# pcb.net
KiCad netlist of a schematic drawn in EasyEDA Pro
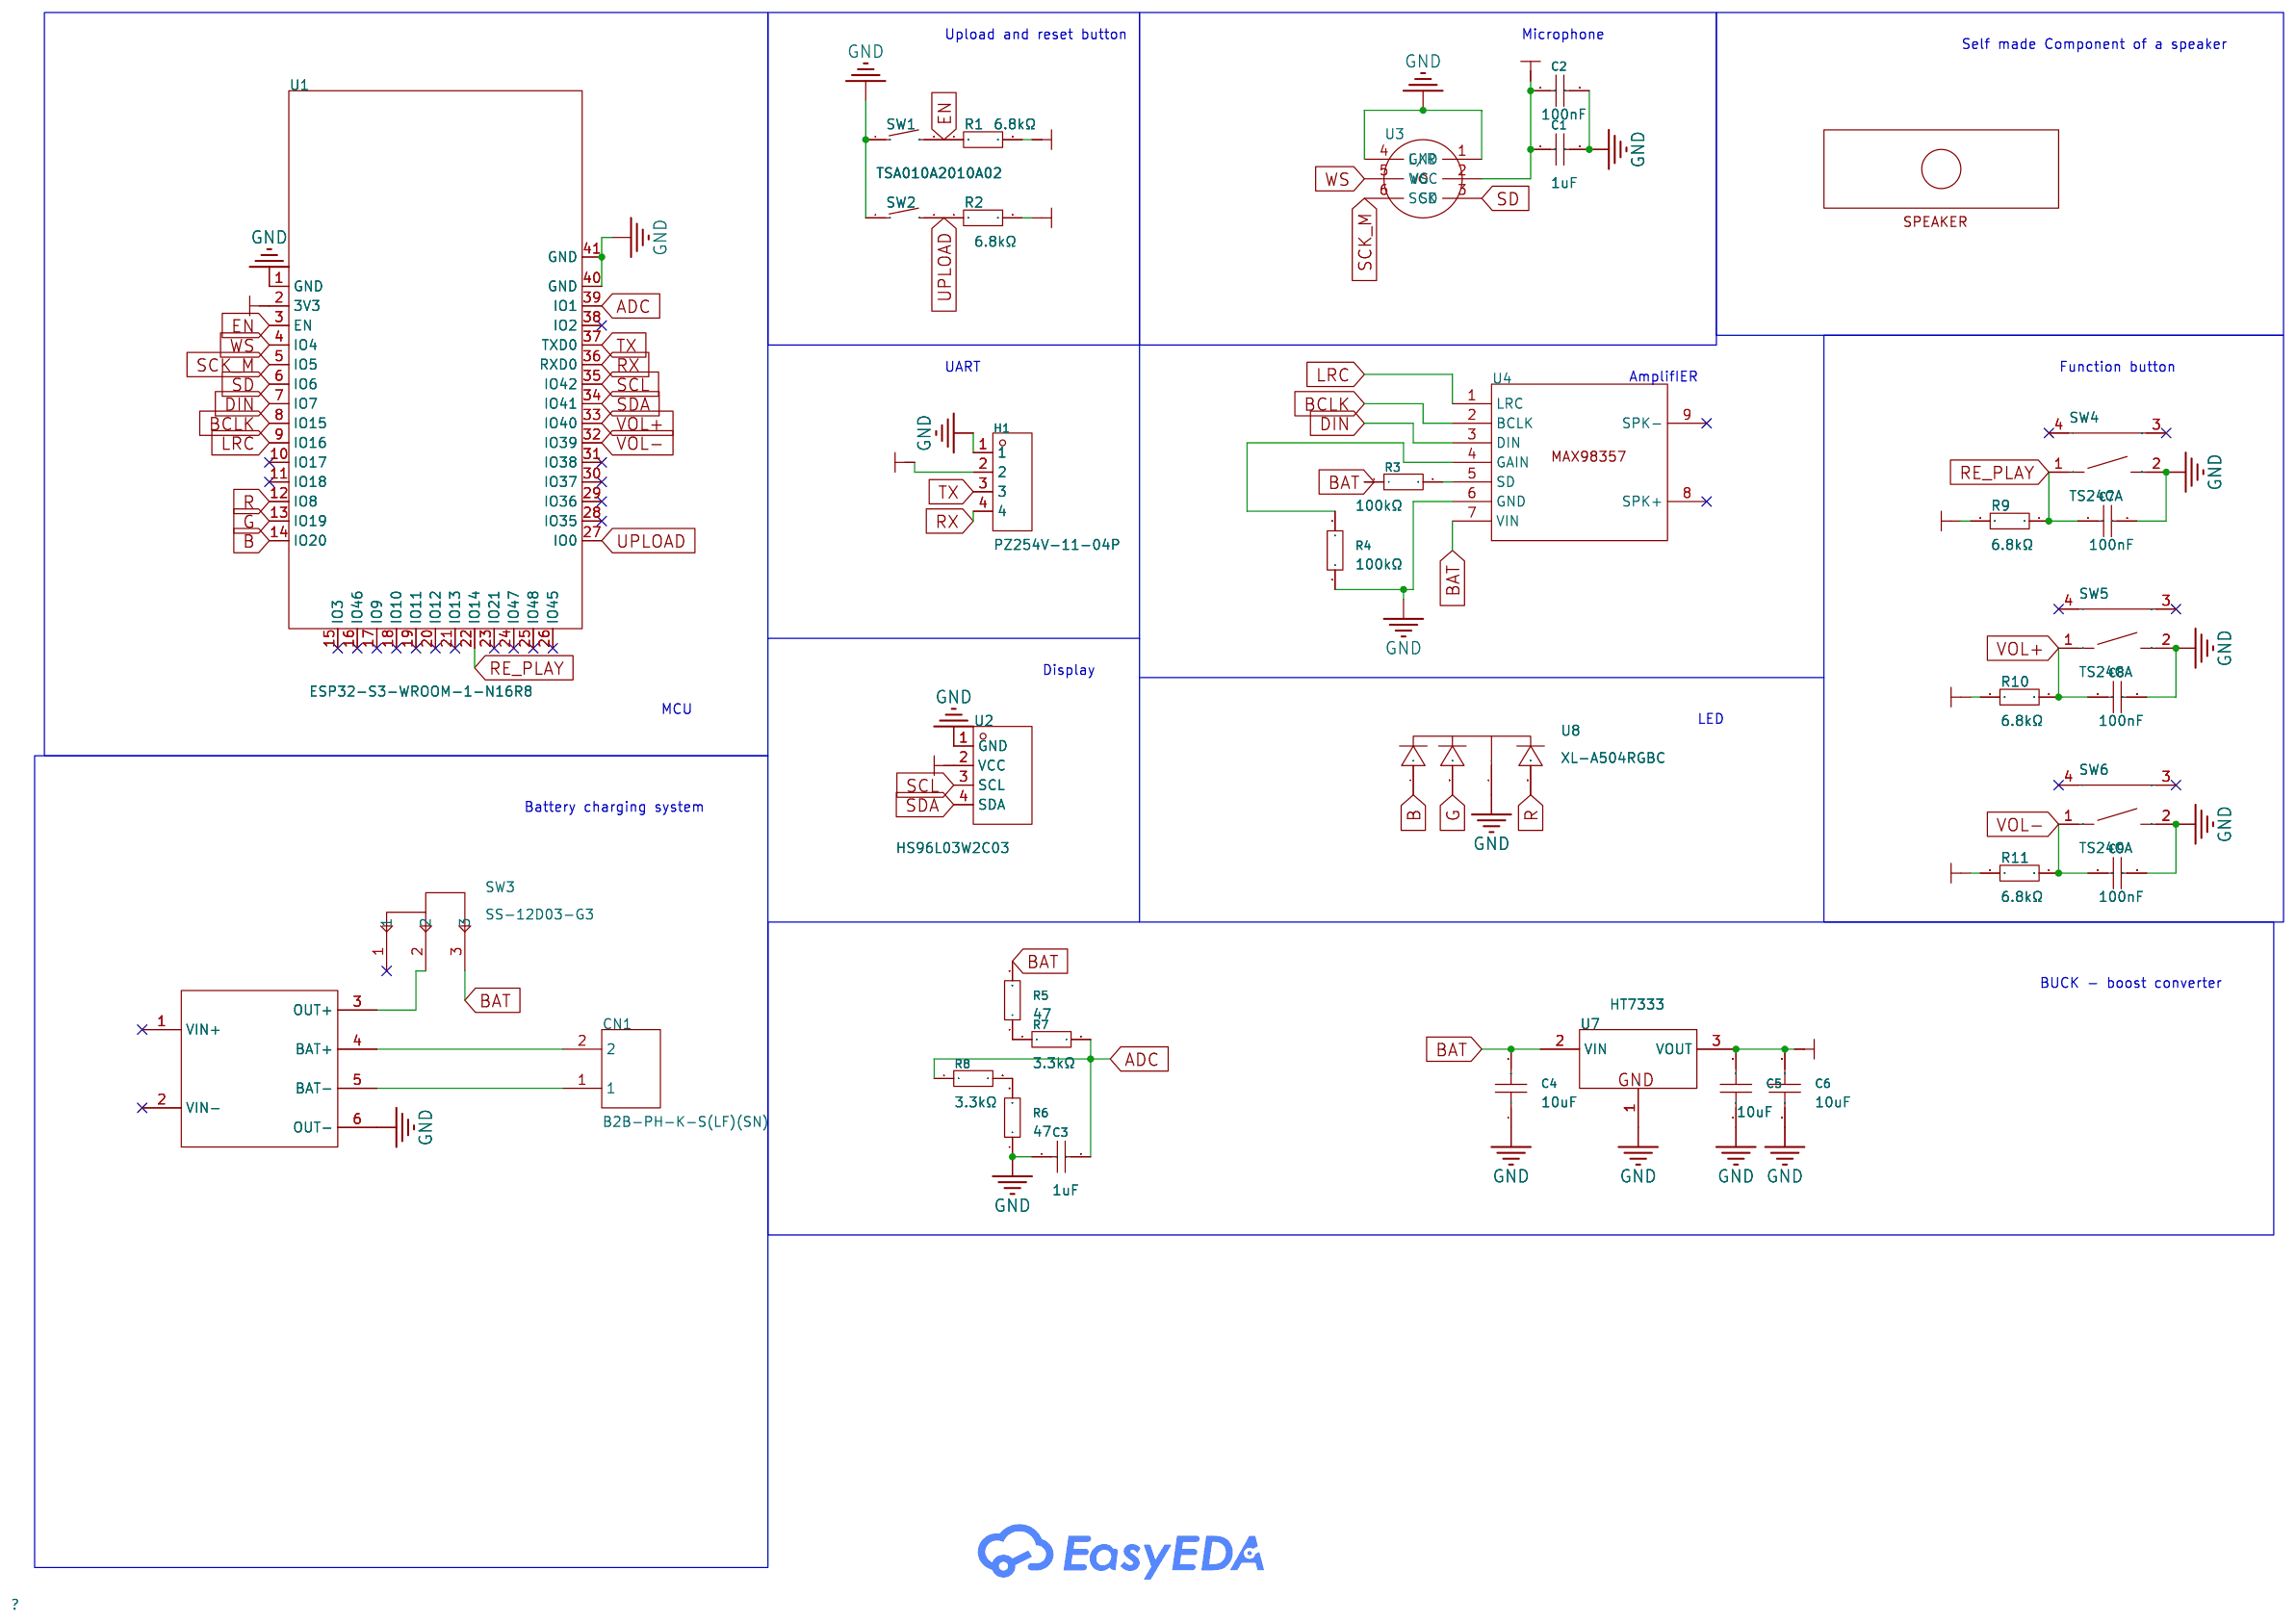
[diagram p0: schematic sheet]

(export (version "E")
  (design (tool "Eeschema 10.0.6"))
  (components
    (comp (ref "C1")
      (value "1uF")
      (footprint "easyedapro:C0805")
      (description "Capacitance:1uF Tolerance:±10% Tolerance:±10% Voltage Rating:50V Temperature Coefficient:X7R")
      (fields
        (field (name "Manufacturer Part") "CL21B105KBFNNNE")
        (field (name "Manufacturer") "SAMSUNG(三星)")
      )
      (libsource (lib "easyedapro") (part "CL21B105KBFNNNE"))
    )
    (comp (ref "C2")
      (value "100nF")
      (footprint "easyedapro:C1206")
      (description "Capacitance:100nF Tolerance:±10% Tolerance:±10% Voltage Rating:50V Temperature Coefficient:X7R")
      (fields
        (field (name "Manufacturer Part") "CL31B104KBCNNNC")
        (field (name "Manufacturer") "SAMSUNG(三星)")
      )
      (libsource (lib "easyedapro") (part "CL31B104KBCNNNC"))
    )
    (comp (ref "C3")
      (value "1uF")
      (footprint "easyedapro:C0805")
      (description "Capacitance:1uF Tolerance:±10% Tolerance:±10% Voltage Rating:50V Temperature Coefficient:X7R")
      (fields
        (field (name "Manufacturer Part") "CL21B105KBFNNNE")
        (field (name "Manufacturer") "SAMSUNG(三星)")
      )
      (libsource (lib "easyedapro") (part "CL21B105KBFNNNE"))
    )
    (comp (ref "C4")
      (value "10uF")
      (footprint "easyedapro:C0603")
      (description "Capacitance:10uF Tolerance:±20% Tolerance:±20% Voltage Rating:25V Temperature Coefficient:X5R")
      (fields
        (field (name "Manufacturer Part") "CL10A106MA8NRNC")
        (field (name "Manufacturer") "SAMSUNG(三星)")
      )
      (libsource (lib "easyedapro") (part "CL10A106MA8NRNC"))
    )
    (comp (ref "C5")
      (value "10uF")
      (footprint "easyedapro:C0603")
      (description "Capacitance:10uF Tolerance:±20% Tolerance:±20% Voltage Rating:25V Temperature Coefficient:X5R")
      (fields
        (field (name "Manufacturer Part") "CL10A106MA8NRNC")
        (field (name "Manufacturer") "SAMSUNG(三星)")
      )
      (libsource (lib "easyedapro") (part "CL10A106MA8NRNC"))
    )
    (comp (ref "C6")
      (value "10uF")
      (footprint "easyedapro:C0603")
      (description "Capacitance:10uF Tolerance:±20% Tolerance:±20% Voltage Rating:25V Temperature Coefficient:X5R")
      (fields
        (field (name "Manufacturer Part") "CL10A106MA8NRNC")
        (field (name "Manufacturer") "SAMSUNG(三星)")
      )
      (libsource (lib "easyedapro") (part "CL10A106MA8NRNC"))
    )
    (comp (ref "C7")
      (value "100nF")
      (footprint "easyedapro:C1206")
      (description "Capacitance:100nF Tolerance:±10% Tolerance:±10% Voltage Rating:50V Temperature Coefficient:X7R")
      (fields
        (field (name "Manufacturer Part") "CL31B104KBCNNNC")
        (field (name "Manufacturer") "SAMSUNG(三星)")
      )
      (libsource (lib "easyedapro") (part "CL31B104KBCNNNC"))
    )
    (comp (ref "C8")
      (value "100nF")
      (footprint "easyedapro:C1206")
      (description "Capacitance:100nF Tolerance:±10% Tolerance:±10% Voltage Rating:50V Temperature Coefficient:X7R")
      (fields
        (field (name "Manufacturer Part") "CL31B104KBCNNNC")
        (field (name "Manufacturer") "SAMSUNG(三星)")
      )
      (libsource (lib "easyedapro") (part "CL31B104KBCNNNC"))
    )
    (comp (ref "C9")
      (value "100nF")
      (footprint "easyedapro:C1206")
      (description "Capacitance:100nF Tolerance:±10% Tolerance:±10% Voltage Rating:50V Temperature Coefficient:X7R")
      (fields
        (field (name "Manufacturer Part") "CL31B104KBCNNNC")
        (field (name "Manufacturer") "SAMSUNG(三星)")
      )
      (libsource (lib "easyedapro") (part "CL31B104KBCNNNC"))
    )
    (comp (ref "CN1")
      (value "B2B-PH-K-S(LF)(SN)")
      (footprint "easyedapro:CONN-TH_B2B-PH-K-S")
      (fields (field (name "Manufacturer") "JST"))
      (libsource (lib "easyedapro") (part "B2B-PH-K-S(LF)(SN)"))
    )
    (comp (ref "H1")
      (value "PZ254V-11-04P")
      (footprint "easyedapro:HDR-TH_4P-P2.54-V-M")
      (fields (field (name "Manufacturer") "XFCN(兴飞)"))
      (libsource (lib "easyedapro") (part "PZ254V-11-04P_C2691448"))
    )
    (comp (ref "R1")
      (value "6.8kΩ")
      (footprint "easyedapro:R0603")
      (fields (field (name "Manufacturer Part") "RC0603FR-071KL") (field (name "Manufacturer") "YAGEO(国巨)"))
      (libsource (lib "easyedapro") (part "RC0603FR-071KL"))
    )
    (comp (ref "R2")
      (value "6.8kΩ")
      (footprint "easyedapro:R0603")
      (fields (field (name "Manufacturer Part") "RC0603FR-071KL") (field (name "Manufacturer") "YAGEO(国巨)"))
      (libsource (lib "easyedapro") (part "RC0603FR-071KL"))
    )
    (comp (ref "R3")
      (value "100kΩ")
      (footprint "easyedapro:R0603")
      (fields (field (name "Manufacturer Part") "RC0603FR-07100KL") (field (name "Manufacturer") "YAGEO(国巨)"))
      (libsource (lib "easyedapro") (part "RC0603FR-07100KL"))
    )
    (comp (ref "R4")
      (value "100kΩ")
      (footprint "easyedapro:R0603")
      (fields (field (name "Manufacturer Part") "RC0603FR-07100KL") (field (name "Manufacturer") "YAGEO(国巨)"))
      (libsource (lib "easyedapro") (part "RC0603FR-07100KL"))
    )
    (comp (ref "R5")
      (value "47")
      (footprint "easyedapro:R1206")
      (fields
        (field (name "Manufacturer Part") "1206W4F100KT5E")
        (field (name "Manufacturer") "UNI-ROYAL(厚声)")
      )
      (libsource (lib "easyedapro") (part "1206W4F100KT5E"))
    )
    (comp (ref "R6")
      (value "47")
      (footprint "easyedapro:R1206")
      (fields
        (field (name "Manufacturer Part") "1206W4F100KT5E")
        (field (name "Manufacturer") "UNI-ROYAL(厚声)")
      )
      (libsource (lib "easyedapro") (part "1206W4F100KT5E"))
    )
    (comp (ref "R7")
      (value "3.3kΩ")
      (footprint "easyedapro:R0603")
      (fields
        (field (name "Manufacturer Part") "0603WAF3301T5E")
        (field (name "Manufacturer") "UNI-ROYAL(厚声)")
      )
      (libsource (lib "easyedapro") (part "0603WAF3301T5E"))
    )
    (comp (ref "R8")
      (value "3.3kΩ")
      (footprint "easyedapro:R0603")
      (fields
        (field (name "Manufacturer Part") "0603WAF3301T5E")
        (field (name "Manufacturer") "UNI-ROYAL(厚声)")
      )
      (libsource (lib "easyedapro") (part "0603WAF3301T5E"))
    )
    (comp (ref "R9")
      (value "6.8kΩ")
      (footprint "easyedapro:R0603")
      (fields (field (name "Manufacturer Part") "RC0603FR-071KL") (field (name "Manufacturer") "YAGEO(国巨)"))
      (libsource (lib "easyedapro") (part "RC0603FR-071KL"))
    )
    (comp (ref "R10")
      (value "6.8kΩ")
      (footprint "easyedapro:R0603")
      (fields (field (name "Manufacturer Part") "RC0603FR-071KL") (field (name "Manufacturer") "YAGEO(国巨)"))
      (libsource (lib "easyedapro") (part "RC0603FR-071KL"))
    )
    (comp (ref "R11")
      (value "6.8kΩ")
      (footprint "easyedapro:R0603")
      (fields (field (name "Manufacturer Part") "RC0603FR-071KL") (field (name "Manufacturer") "YAGEO(国巨)"))
      (libsource (lib "easyedapro") (part "RC0603FR-071KL"))
    )
    (comp (ref "SW1")
      (value "TSA010A2010A02")
      (footprint "easyedapro:KEY-SMD_L3.9-W3.0-LS5.0")
      (fields (field (name "Manufacturer") "BZCN(博众电气)"))
      (libsource (lib "easyedapro") (part "TSA010A2010A02"))
    )
    (comp (ref "SW2")
      (value "TSA010A2010A02")
      (footprint "easyedapro:KEY-SMD_L3.9-W3.0-LS5.0")
      (fields (field (name "Manufacturer") "BZCN(博众电气)"))
      (libsource (lib "easyedapro") (part "TSA010A2010A02"))
    )
    (comp (ref "SW3")
      (value "SS-12D03-G3")
      (footprint "easyedapro:SW-TH_3P-L8.5-W3.5-P2.50_SS-12D03-G3_C5160828")
      (fields (field (name "Manufacturer") "DEALON(德艺隆)"))
      (libsource (lib "easyedapro") (part "SS-12D03-G3_C5160828"))
    )
    (comp (ref "SW4")
      (value "TS24CA")
      (footprint "easyedapro:SW-SMD_2P-TS24CA")
      (fields (field (name "Manufacturer") "SHOU HAN(首韩)"))
      (libsource (lib "easyedapro") (part "TS24CA"))
    )
    (comp (ref "SW5")
      (value "TS24CA")
      (footprint "easyedapro:SW-SMD_2P-TS24CA")
      (fields (field (name "Manufacturer") "SHOU HAN(首韩)"))
      (libsource (lib "easyedapro") (part "TS24CA"))
    )
    (comp (ref "SW6")
      (value "TS24CA")
      (footprint "easyedapro:SW-SMD_2P-TS24CA")
      (fields (field (name "Manufacturer") "SHOU HAN(首韩)"))
      (libsource (lib "easyedapro") (part "TS24CA"))
    )
    (comp (ref "U1")
      (value "ESP32-S3-WROOM-1-N16R8")
      (footprint "easyedapro:WIRELM-SMD_ESP32-S3-WROOM-1")
      (fields (field (name "Manufacturer") "ESPRESSIF(乐鑫)"))
      (libsource (lib "easyedapro") (part "ESP32-S3-WROOM-1(N16R8)"))
    )
    (comp (ref "U2")
      (value "HS96L03W2C03")
      (footprint "easyedapro:OLED-TH_L27.8-W27.2-P2.54_C9900033791")
      (fields (field (name "Manufacturer") "HS(汉昇)"))
      (libsource (lib "easyedapro") (part "HS96L03W2C03"))
    )
    (comp (ref "U3")
      (value "~")
      (footprint "easyedapro:INMP441")
      (libsource (lib "easyedapro") (part "INMP441"))
    )
    (comp (ref "U4")
      (value "~")
      (footprint "easyedapro:MAX98357")
      (libsource (lib "easyedapro") (part "MAX98357"))
    )
    (comp (ref "U5")
      (value "~")
      (footprint "easyedapro:SPEAKER")
      (libsource (lib "easyedapro") (part "SPEAKER"))
    )
    (comp (ref "U6")
      (value "~")
      (footprint "easyedapro:TP4056 Carging Module")
      (libsource (lib "easyedapro") (part "TP4056 Charging Module"))
    )
    (comp (ref "U7")
      (value "HT7333")
      (footprint "easyedapro:SOT-89-3_L4.5-W2.5-P1.50-LS4.1-BR")
      (description "Output Type:-")
      (libsource (lib "easyedapro") (part "HT7333"))
    )
    (comp (ref "U8")
      (value "XL-A504RGBC")
      (footprint "easyedapro:LED-TH_4P-BD5.8-P1.25_DM-50346EH-73826CC-05RGB-BML60-D")
      (fields (field (name "Manufacturer") "XINGLIGHT(成兴光)"))
      (libsource (lib "easyedapro") (part "XL-A504RGBC"))
    )
  )
  (nets
    (net (code "1") (name "+3V3") (class "Default")
      (node (ref "C1") (pin "1") (pinfunction "1_1") (pintype "input"))
      (node (ref "C2") (pin "1") (pinfunction "1_1") (pintype "input"))
      (node (ref "C5") (pin "2") (pinfunction "2_2") (pintype "input"))
      (node (ref "C6") (pin "2") (pinfunction "2_2") (pintype "input"))
      (node (ref "H1") (pin "2") (pinfunction "2_2") (pintype "input"))
      (node (ref "R1") (pin "2") (pinfunction "2_2") (pintype "input"))
      (node (ref "R10") (pin "2") (pinfunction "2_2") (pintype "input"))
      (node (ref "R11") (pin "2") (pinfunction "2_2") (pintype "input"))
      (node (ref "R2") (pin "2") (pinfunction "2_2") (pintype "input"))
      (node (ref "R9") (pin "2") (pinfunction "2_2") (pintype "input"))
      (node (ref "U1") (pin "2") (pinfunction "3V3_2") (pintype "unspecified"))
      (node (ref "U2") (pin "2") (pinfunction "VCC_2") (pintype "unspecified"))
      (node (ref "U3") (pin "2") (pinfunction "VCC_2") (pintype "input"))
      (node (ref "U7") (pin "3") (pinfunction "VOUT_3") (pintype "unspecified"))
    )
    (net (code "2") (name "ADC") (class "Default")
      (node (ref "C3") (pin "2") (pinfunction "2_2") (pintype "input"))
      (node (ref "R7") (pin "2") (pinfunction "2_2") (pintype "input"))
      (node (ref "R8") (pin "1") (pinfunction "1_1") (pintype "input"))
      (node (ref "U1") (pin "39") (pinfunction "IO1_39") (pintype "unspecified"))
    )
    (net (code "3") (name "B") (class "Default")
      (node (ref "U1") (pin "14") (pinfunction "IO20_14") (pintype "unspecified"))
      (node (ref "U8") (pin "4") (pinfunction "4_4") (pintype "unspecified"))
    )
    (net (code "4") (name "BAT") (class "Default")
      (node (ref "C4") (pin "2") (pinfunction "2_2") (pintype "input"))
      (node (ref "R3") (pin "1") (pinfunction "1_1") (pintype "input"))
      (node (ref "R5") (pin "2") (pinfunction "2_2") (pintype "input"))
      (node (ref "SW3") (pin "3") (pinfunction "3_3") (pintype "unspecified"))
      (node (ref "U4") (pin "7") (pinfunction "VIN_7") (pintype "input"))
      (node (ref "U7") (pin "2") (pinfunction "VIN_2") (pintype "unspecified"))
    )
    (net (code "5") (name "BCLK") (class "Default")
      (node (ref "U1") (pin "8") (pinfunction "IO15_8") (pintype "unspecified"))
      (node (ref "U4") (pin "2") (pinfunction "BCLK_2") (pintype "input"))
    )
    (net (code "6") (name "DIN") (class "Default")
      (node (ref "U1") (pin "7") (pinfunction "IO7_7") (pintype "unspecified"))
      (node (ref "U4") (pin "3") (pinfunction "DIN_3") (pintype "input"))
    )
    (net (code "7") (name "EN") (class "Default")
      (node (ref "R1") (pin "1") (pinfunction "1_1") (pintype "input"))
      (node (ref "SW1") (pin "2") (pinfunction "2_2") (pintype "unspecified"))
      (node (ref "U1") (pin "3") (pinfunction "EN_3") (pintype "unspecified"))
    )
    (net (code "8") (name "G") (class "Default")
      (node (ref "U1") (pin "13") (pinfunction "IO19_13") (pintype "unspecified"))
      (node (ref "U8") (pin "3") (pinfunction "3_3") (pintype "unspecified"))
    )
    (net (code "9") (name "GND") (class "Default")
      (node (ref "C1") (pin "2") (pinfunction "2_2") (pintype "input"))
      (node (ref "C2") (pin "2") (pinfunction "2_2") (pintype "input"))
      (node (ref "C3") (pin "1") (pinfunction "1_1") (pintype "input"))
      (node (ref "C4") (pin "1") (pinfunction "1_1") (pintype "input"))
      (node (ref "C5") (pin "1") (pinfunction "1_1") (pintype "input"))
      (node (ref "C6") (pin "1") (pinfunction "1_1") (pintype "input"))
      (node (ref "C7") (pin "2") (pinfunction "2_2") (pintype "input"))
      (node (ref "C8") (pin "2") (pinfunction "2_2") (pintype "input"))
      (node (ref "C9") (pin "2") (pinfunction "2_2") (pintype "input"))
      (node (ref "H1") (pin "1") (pinfunction "1_1") (pintype "input"))
      (node (ref "R4") (pin "1") (pinfunction "1_1") (pintype "input"))
      (node (ref "R6") (pin "1") (pinfunction "1_1") (pintype "input"))
      (node (ref "SW1") (pin "1") (pinfunction "1_1") (pintype "unspecified"))
      (node (ref "SW2") (pin "1") (pinfunction "1_1") (pintype "unspecified"))
      (node (ref "SW4") (pin "2") (pinfunction "2_2") (pintype "unspecified"))
      (node (ref "SW5") (pin "2") (pinfunction "2_2") (pintype "unspecified"))
      (node (ref "SW6") (pin "2") (pinfunction "2_2") (pintype "unspecified"))
      (node (ref "U1") (pin "1") (pinfunction "GND_1") (pintype "unspecified"))
      (node (ref "U1") (pin "40") (pinfunction "GND_40") (pintype "unspecified"))
      (node (ref "U1") (pin "41") (pinfunction "GND_41") (pintype "unspecified"))
      (node (ref "U2") (pin "1") (pinfunction "GND_1") (pintype "unspecified"))
      (node (ref "U3") (pin "1") (pinfunction "GND_1") (pintype "input"))
      (node (ref "U3") (pin "4") (pinfunction "L/R_4") (pintype "input"))
      (node (ref "U4") (pin "6") (pinfunction "GND_6") (pintype "input"))
      (node (ref "U6") (pin "6") (pinfunction "OUT-_6") (pintype "input"))
      (node (ref "U7") (pin "1") (pinfunction "GND_1") (pintype "unspecified"))
      (node (ref "U8") (pin "1") (pinfunction "-_1") (pintype "unspecified"))
    )
    (net (code "10") (name "LRC") (class "Default")
      (node (ref "U1") (pin "9") (pinfunction "IO16_9") (pintype "unspecified"))
      (node (ref "U4") (pin "1") (pinfunction "LRC_1") (pintype "input"))
    )
    (net (code "11") (name "Net-(R5-Pad1)") (class "Default")
      (node (ref "R5") (pin "1") (pinfunction "1_1") (pintype "input"))
      (node (ref "R7") (pin "1") (pinfunction "1_1") (pintype "input"))
    )
    (net (code "12") (name "Net-(R6-Pad2)") (class "Default")
      (node (ref "R6") (pin "2") (pinfunction "2_2") (pintype "input"))
      (node (ref "R8") (pin "2") (pinfunction "2_2") (pintype "input"))
    )
    (net (code "13") (name "Net-(U4-GAIN)") (class "Default")
      (node (ref "R4") (pin "2") (pinfunction "2_2") (pintype "input"))
      (node (ref "U4") (pin "4") (pinfunction "GAIN_4") (pintype "input"))
    )
    (net (code "14") (name "Net-(U4-SD)") (class "Default")
      (node (ref "R3") (pin "2") (pinfunction "2_2") (pintype "input"))
      (node (ref "U4") (pin "5") (pinfunction "SD_5") (pintype "input"))
    )
    (net (code "15") (name "Net-(U6-BAT+)") (class "Default")
      (node (ref "CN1") (pin "2") (pinfunction "2_2") (pintype "input"))
      (node (ref "U6") (pin "4") (pinfunction "BAT+_4") (pintype "input"))
    )
    (net (code "16") (name "Net-(U6-BAT-)") (class "Default")
      (node (ref "CN1") (pin "1") (pinfunction "1_1") (pintype "input"))
      (node (ref "U6") (pin "5") (pinfunction "BAT-_5") (pintype "input"))
    )
    (net (code "17") (name "Net-(U6-OUT+)") (class "Default")
      (node (ref "SW3") (pin "2") (pinfunction "2_2") (pintype "unspecified"))
      (node (ref "U6") (pin "3") (pinfunction "OUT+_3") (pintype "input"))
    )
    (net (code "18") (name "R") (class "Default")
      (node (ref "U1") (pin "12") (pinfunction "IO8_12") (pintype "unspecified"))
      (node (ref "U8") (pin "2") (pinfunction "2_2") (pintype "unspecified"))
    )
    (net (code "19") (name "RE_PLAY") (class "Default")
      (node (ref "C7") (pin "1") (pinfunction "1_1") (pintype "input"))
      (node (ref "R9") (pin "1") (pinfunction "1_1") (pintype "input"))
      (node (ref "SW4") (pin "1") (pinfunction "1_1") (pintype "unspecified"))
      (node (ref "U1") (pin "22") (pinfunction "IO14_22") (pintype "unspecified"))
    )
    (net (code "20") (name "RX") (class "Default")
      (node (ref "H1") (pin "4") (pinfunction "4_4") (pintype "input"))
      (node (ref "U1") (pin "36") (pinfunction "RXD0_36") (pintype "unspecified"))
    )
    (net (code "21") (name "SCK_M") (class "Default")
      (node (ref "U1") (pin "5") (pinfunction "IO5_5") (pintype "unspecified"))
      (node (ref "U3") (pin "6") (pinfunction "SCK_6") (pintype "input"))
    )
    (net (code "22") (name "SCL") (class "Default")
      (node (ref "U1") (pin "35") (pinfunction "IO42_35") (pintype "unspecified"))
      (node (ref "U2") (pin "3") (pinfunction "SCL_3") (pintype "unspecified"))
    )
    (net (code "23") (name "SD") (class "Default")
      (node (ref "U1") (pin "6") (pinfunction "IO6_6") (pintype "unspecified"))
      (node (ref "U3") (pin "3") (pinfunction "SD_3") (pintype "input"))
    )
    (net (code "24") (name "SDA") (class "Default")
      (node (ref "U1") (pin "34") (pinfunction "IO41_34") (pintype "unspecified"))
      (node (ref "U2") (pin "4") (pinfunction "SDA_4") (pintype "unspecified"))
    )
    (net (code "25") (name "TX") (class "Default")
      (node (ref "H1") (pin "3") (pinfunction "3_3") (pintype "input"))
      (node (ref "U1") (pin "37") (pinfunction "TXD0_37") (pintype "unspecified"))
    )
    (net (code "26") (name "UPLOAD") (class "Default")
      (node (ref "R2") (pin "1") (pinfunction "1_1") (pintype "input"))
      (node (ref "SW2") (pin "2") (pinfunction "2_2") (pintype "unspecified"))
      (node (ref "U1") (pin "27") (pinfunction "IO0_27") (pintype "unspecified"))
    )
    (net (code "27") (name "VOL+") (class "Default")
      (node (ref "C8") (pin "1") (pinfunction "1_1") (pintype "input"))
      (node (ref "R10") (pin "1") (pinfunction "1_1") (pintype "input"))
      (node (ref "SW5") (pin "1") (pinfunction "1_1") (pintype "unspecified"))
      (node (ref "U1") (pin "33") (pinfunction "IO40_33") (pintype "unspecified"))
    )
    (net (code "28") (name "VOL-") (class "Default")
      (node (ref "C9") (pin "1") (pinfunction "1_1") (pintype "input"))
      (node (ref "R11") (pin "1") (pinfunction "1_1") (pintype "input"))
      (node (ref "SW6") (pin "1") (pinfunction "1_1") (pintype "unspecified"))
      (node (ref "U1") (pin "32") (pinfunction "IO39_32") (pintype "unspecified"))
    )
    (net (code "29") (name "WS") (class "Default")
      (node (ref "U1") (pin "4") (pinfunction "IO4_4") (pintype "unspecified"))
      (node (ref "U3") (pin "5") (pinfunction "WS_5") (pintype "input"))
    )
    (net (code "30") (name "unconnected-(SW3-Pad1)") (class "Default")
      (node (ref "SW3") (pin "1") (pinfunction "1_1") (pintype "unspecified+no_connect"))
    )
    (net (code "31") (name "unconnected-(SW4-Pad3)") (class "Default")
      (node (ref "SW4") (pin "3") (pinfunction "3_3") (pintype "unspecified+no_connect"))
    )
    (net (code "32") (name "unconnected-(SW4-Pad4)") (class "Default")
      (node (ref "SW4") (pin "4") (pinfunction "4_4") (pintype "unspecified+no_connect"))
    )
    (net (code "33") (name "unconnected-(SW5-Pad3)") (class "Default")
      (node (ref "SW5") (pin "3") (pinfunction "3_3") (pintype "unspecified+no_connect"))
    )
    (net (code "34") (name "unconnected-(SW5-Pad4)") (class "Default")
      (node (ref "SW5") (pin "4") (pinfunction "4_4") (pintype "unspecified+no_connect"))
    )
    (net (code "35") (name "unconnected-(SW6-Pad3)") (class "Default")
      (node (ref "SW6") (pin "3") (pinfunction "3_3") (pintype "unspecified+no_connect"))
    )
    (net (code "36") (name "unconnected-(SW6-Pad4)") (class "Default")
      (node (ref "SW6") (pin "4") (pinfunction "4_4") (pintype "unspecified+no_connect"))
    )
    (net (code "37") (name "unconnected-(U1-IO2-Pad38)") (class "Default")
      (node (ref "U1") (pin "38") (pinfunction "IO2_38") (pintype "unspecified+no_connect"))
    )
    (net (code "38") (name "unconnected-(U1-IO3-Pad15)") (class "Default")
      (node (ref "U1") (pin "15") (pinfunction "IO3_15") (pintype "unspecified+no_connect"))
    )
    (net (code "39") (name "unconnected-(U1-IO9-Pad17)") (class "Default")
      (node (ref "U1") (pin "17") (pinfunction "IO9_17") (pintype "unspecified+no_connect"))
    )
    (net (code "40") (name "unconnected-(U1-IO10-Pad18)") (class "Default")
      (node (ref "U1") (pin "18") (pinfunction "IO10_18") (pintype "unspecified+no_connect"))
    )
    (net (code "41") (name "unconnected-(U1-IO11-Pad19)") (class "Default")
      (node (ref "U1") (pin "19") (pinfunction "IO11_19") (pintype "unspecified+no_connect"))
    )
    (net (code "42") (name "unconnected-(U1-IO12-Pad20)") (class "Default")
      (node (ref "U1") (pin "20") (pinfunction "IO12_20") (pintype "unspecified+no_connect"))
    )
    (net (code "43") (name "unconnected-(U1-IO13-Pad21)") (class "Default")
      (node (ref "U1") (pin "21") (pinfunction "IO13_21") (pintype "unspecified+no_connect"))
    )
    (net (code "44") (name "unconnected-(U1-IO17-Pad10)") (class "Default")
      (node (ref "U1") (pin "10") (pinfunction "IO17_10") (pintype "unspecified+no_connect"))
    )
    (net (code "45") (name "unconnected-(U1-IO18-Pad11)") (class "Default")
      (node (ref "U1") (pin "11") (pinfunction "IO18_11") (pintype "unspecified+no_connect"))
    )
    (net (code "46") (name "unconnected-(U1-IO21-Pad23)") (class "Default")
      (node (ref "U1") (pin "23") (pinfunction "IO21_23") (pintype "unspecified+no_connect"))
    )
    (net (code "47") (name "unconnected-(U1-IO35-Pad28)") (class "Default")
      (node (ref "U1") (pin "28") (pinfunction "IO35_28") (pintype "unspecified+no_connect"))
    )
    (net (code "48") (name "unconnected-(U1-IO36-Pad29)") (class "Default")
      (node (ref "U1") (pin "29") (pinfunction "IO36_29") (pintype "unspecified+no_connect"))
    )
    (net (code "49") (name "unconnected-(U1-IO37-Pad30)") (class "Default")
      (node (ref "U1") (pin "30") (pinfunction "IO37_30") (pintype "unspecified+no_connect"))
    )
    (net (code "50") (name "unconnected-(U1-IO38-Pad31)") (class "Default")
      (node (ref "U1") (pin "31") (pinfunction "IO38_31") (pintype "unspecified+no_connect"))
    )
    (net (code "51") (name "unconnected-(U1-IO45-Pad26)") (class "Default")
      (node (ref "U1") (pin "26") (pinfunction "IO45_26") (pintype "unspecified+no_connect"))
    )
    (net (code "52") (name "unconnected-(U1-IO46-Pad16)") (class "Default")
      (node (ref "U1") (pin "16") (pinfunction "IO46_16") (pintype "unspecified+no_connect"))
    )
    (net (code "53") (name "unconnected-(U1-IO47-Pad24)") (class "Default")
      (node (ref "U1") (pin "24") (pinfunction "IO47_24") (pintype "unspecified+no_connect"))
    )
    (net (code "54") (name "unconnected-(U1-IO48-Pad25)") (class "Default")
      (node (ref "U1") (pin "25") (pinfunction "IO48_25") (pintype "unspecified+no_connect"))
    )
    (net (code "55") (name "unconnected-(U4-SPK+-Pad8)") (class "Default")
      (node (ref "U4") (pin "8") (pinfunction "SPK+_8") (pintype "input+no_connect"))
    )
    (net (code "56") (name "unconnected-(U4-SPK--Pad9)") (class "Default")
      (node (ref "U4") (pin "9") (pinfunction "SPK-_9") (pintype "input+no_connect"))
    )
    (net (code "57") (name "unconnected-(U6-VIN+-Pad1)") (class "Default")
      (node (ref "U6") (pin "1") (pinfunction "VIN+_1") (pintype "input+no_connect"))
    )
    (net (code "58") (name "unconnected-(U6-VIN--Pad2)") (class "Default")
      (node (ref "U6") (pin "2") (pinfunction "VIN-_2") (pintype "input+no_connect"))
    )
  )
)
